# LED_Indicator.net
KiCad netlist of a schematic drawn in Altium Designer
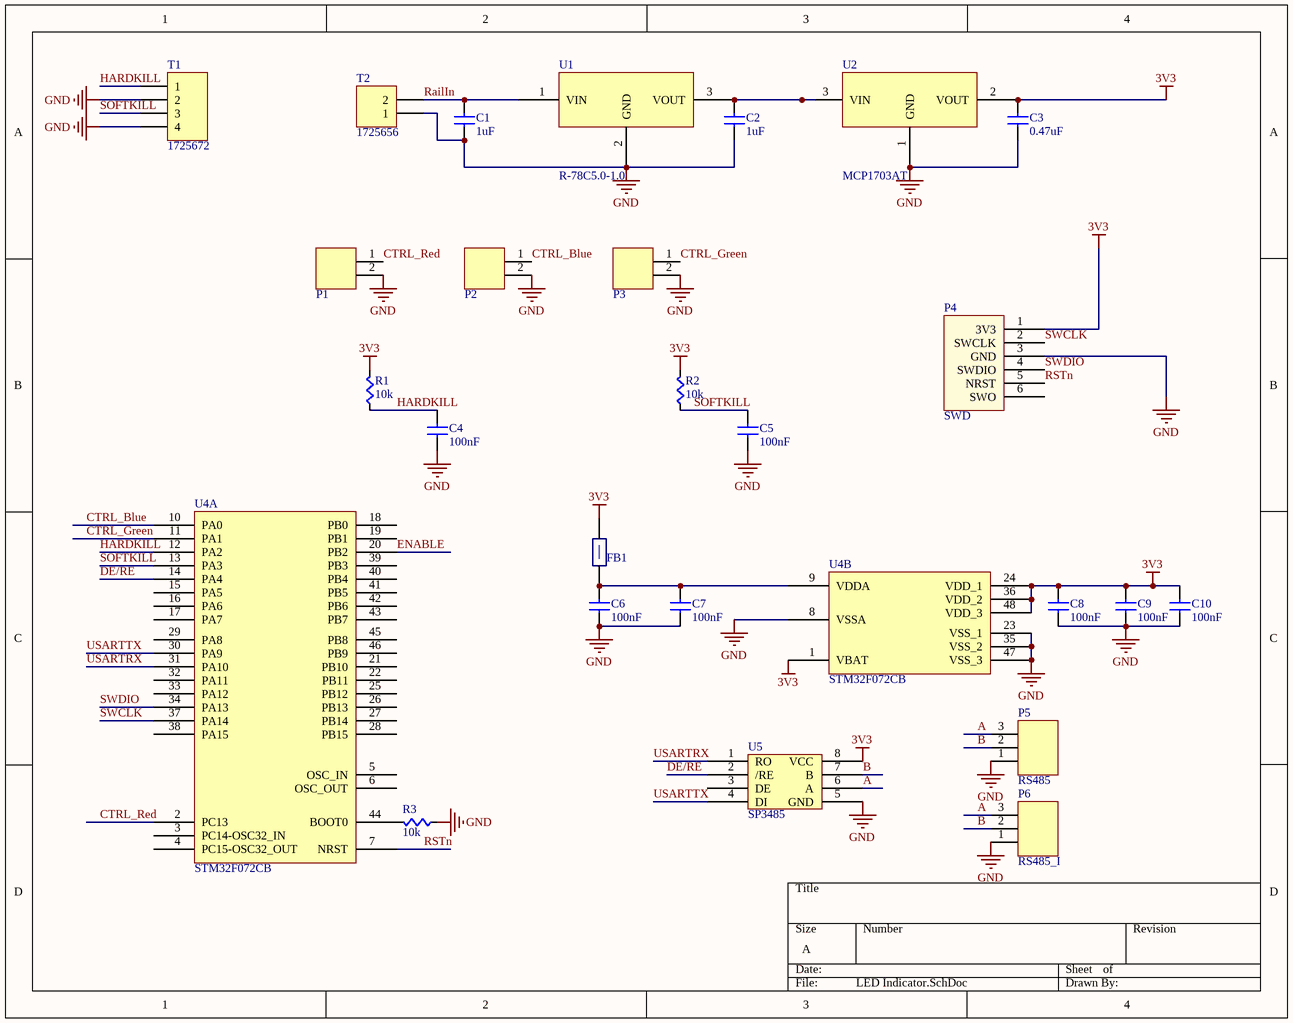
[diagram p0: LED Indicator.SchDoc]

(export (version "E")
  (design (tool "Eeschema 10.0.6"))
  (components
    (comp (ref "C1")
      (value "1uF")
      (footprint "CAPC0603")
      (fields (field (name "Comment") "Cap"))
      (libsource (lib "SubjuGator8") (part "Cap"))
    )
    (comp (ref "C2")
      (value "1uF")
      (footprint "CAPC0603")
      (fields (field (name "Comment") "Cap"))
      (libsource (lib "SubjuGator8") (part "Cap"))
    )
    (comp (ref "C3")
      (value "0.47uF")
      (footprint "CAPC0603")
      (fields (field (name "Comment") "Cap"))
      (libsource (lib "SubjuGator8") (part "Cap"))
    )
    (comp (ref "C4")
      (value "100nF")
      (footprint "CAPC0603")
      (fields (field (name "Comment") "Cap"))
      (libsource (lib "SubjuGator8") (part "Cap"))
    )
    (comp (ref "C5")
      (value "100nF")
      (footprint "CAPC0603")
      (fields (field (name "Comment") "Cap"))
      (libsource (lib "SubjuGator8") (part "Cap"))
    )
    (comp (ref "C6")
      (value "100nF")
      (footprint "CAPC0603")
      (fields (field (name "Comment") "Cap"))
      (libsource (lib "SubjuGator8") (part "Cap"))
    )
    (comp (ref "C7")
      (value "100nF")
      (footprint "CAPC0603")
      (fields (field (name "Comment") "Cap"))
      (libsource (lib "SubjuGator8") (part "Cap"))
    )
    (comp (ref "C8")
      (value "100nF")
      (footprint "CAPC0603")
      (fields (field (name "Comment") "Cap"))
      (libsource (lib "SubjuGator8") (part "Cap"))
    )
    (comp (ref "C9")
      (value "100nF")
      (footprint "CAPC0603")
      (fields (field (name "Comment") "Cap"))
      (libsource (lib "SubjuGator8") (part "Cap"))
    )
    (comp (ref "C10")
      (value "100nF")
      (footprint "CAPC0603")
      (fields (field (name "Comment") "Cap"))
      (libsource (lib "SubjuGator8") (part "Cap"))
    )
    (comp (ref "FB1")
      (value "FBead")
      (footprint "RES0603")
      (description "Ferrite Bead")
      (libsource (lib "SubjuGator8") (part "FBead"))
    )
    (comp (ref "P1")
      (value "2-pin Horz Sherlock")
      (footprint "MOLEX-HDR-1X2-SHERLOCK-HORZ")
      (fields
        (field (name "MANUFACTURER PART NUMBER") "0353630260")
        (field (name "MANUFACTURER") "Molex Inc")
      )
      (libsource (lib "SubjuGator8") (part "MOLEX-HDR-1x2-SHERLOCK_RA"))
    )
    (comp (ref "P2")
      (value "2-pin Horz Sherlock")
      (footprint "MOLEX-HDR-1X2-SHERLOCK-HORZ")
      (fields
        (field (name "MANUFACTURER PART NUMBER") "0353630260")
        (field (name "MANUFACTURER") "Molex Inc")
      )
      (libsource (lib "SubjuGator8") (part "MOLEX-HDR-1x2-SHERLOCK_RA"))
    )
    (comp (ref "P3")
      (value "2-pin Horz Sherlock")
      (footprint "MOLEX-HDR-1X2-SHERLOCK-HORZ")
      (fields
        (field (name "MANUFACTURER PART NUMBER") "0353630260")
        (field (name "MANUFACTURER") "Molex Inc")
      )
      (libsource (lib "SubjuGator8") (part "MOLEX-HDR-1x2-SHERLOCK_RA"))
    )
    (comp (ref "P4")
      (value "SWD")
      (footprint "SWD_STM32")
      (description "SWD connector matching the pinout on STM Discovery Boards")
      (libsource (lib "SubjuGator8") (part "SWD_STM32"))
    )
    (comp (ref "P5")
      (value "RS485")
      (footprint "MOLEX-HDR-1X3-SHERLOCK-RA")
      (description "Header, Molex, 2mm Pitch Sherlock Header, Single Row, Right Angle 3 Circuits, Length 3.3mm")
      (fields
        (field (name "MANUFACTURER PART NUMBER") "35363-0360")
        (field (name "MANUFACTURER") "Molex Connector Corporation")
      )
      (libsource (lib "SubjuGator8") (part "MOLEX-HDR-1x3-SHERLOCK_RA"))
    )
    (comp (ref "P6")
      (value "RS485_I")
      (footprint "MOLEX-HDR-1X3-SHERLOCK-RA")
      (description "Header, Molex, 2mm Pitch Sherlock Header, Single Row, Right Angle 3 Circuits, Length 3.3mm")
      (fields
        (field (name "MANUFACTURER PART NUMBER") "35363-0360")
        (field (name "MANUFACTURER") "Molex Connector Corporation")
      )
      (libsource (lib "SubjuGator8") (part "MOLEX-HDR-1x3-SHERLOCK_RA"))
    )
    (comp (ref "R1")
      (value "10k")
      (footprint "RES0603")
      (fields (field (name "Comment") "Res"))
      (libsource (lib "SubjuGator8") (part "Res"))
    )
    (comp (ref "R2")
      (value "10k")
      (footprint "RES0603")
      (fields (field (name "Comment") "Res"))
      (libsource (lib "SubjuGator8") (part "Res"))
    )
    (comp (ref "R3")
      (value "10k")
      (footprint "RES0603")
      (fields (field (name "Comment") "Res"))
      (libsource (lib "SubjuGator8") (part "Res"))
    )
    (comp (ref "T1")
      (value "1725672")
      (footprint "1725672")
      (description "CONN TERM BLOCK 2.54MM 4POS")
      (libsource (lib "SubjuGator8") (part "1725672"))
    )
    (comp (ref "T2")
      (value "1725656")
      (footprint "1725656")
      (description "CONN TERM BLOCK 2.54MM 2POS")
      (libsource (lib "SubjuGator8") (part "1725656"))
    )
    (comp (ref "U1")
      (value "R-78C5.0-1.0")
      (footprint "R-78C5.0-1.0")
      (description "CONV DC/DC 1A 5V OUT SIP VERT")
      (libsource (lib "SubjuGator8") (part "R-78C5.0-1.0"))
    )
    (comp (ref "U2")
      (value "MCP1703AT")
      (footprint "MCP1703AT-xx02EDB")
      (description "250 mA, 16V, Low Quiescent Current LDO Regulator")
      (libsource (lib "SubjuGator8") (part "MCP1703AT"))
    )
    (comp (ref "U4")
      (value "STM32F072CB")
      (footprint "STM32F072CB")
      (description "MCU 32BIT 128KB FLASH 48LQFP")
      (libsource (lib "SubjuGator8") (part "STM32F072CB"))
    )
    (comp (ref "U5")
      (value "SP3485")
      (footprint "SP3485")
      (description "IC TXRX RS485 HALF DUPLEX 8NSOIC")
      (libsource (lib "SubjuGator8") (part "SP3485"))
    )
  )
  (nets
    (net (code "1") (name "/A") (class "Default")
      (node (ref "P5") (pin "3") (pinfunction "3_3") (pintype "passive"))
      (node (ref "P6") (pin "3") (pinfunction "3_3") (pintype "passive"))
      (node (ref "U5") (pin "6") (pinfunction "A_6") (pintype "passive"))
    )
    (net (code "2") (name "/B") (class "Default")
      (node (ref "P5") (pin "2") (pinfunction "2_2") (pintype "passive"))
      (node (ref "P6") (pin "2") (pinfunction "2_2") (pintype "passive"))
      (node (ref "U5") (pin "7") (pinfunction "B_7") (pintype "passive"))
    )
    (net (code "3") (name "/CTRL_Blue") (class "Default")
      (node (ref "P2") (pin "1") (pinfunction "1_1") (pintype "passive"))
      (node (ref "U4") (pin "10") (pinfunction "PA0_10") (pintype "passive"))
    )
    (net (code "4") (name "/CTRL_Green") (class "Default")
      (node (ref "P3") (pin "1") (pinfunction "1_1") (pintype "passive"))
      (node (ref "U4") (pin "11") (pinfunction "PA1_11") (pintype "passive"))
    )
    (net (code "5") (name "/CTRL_Red") (class "Default")
      (node (ref "P1") (pin "1") (pinfunction "1_1") (pintype "passive"))
      (node (ref "U4") (pin "2") (pinfunction "PC13_2") (pintype "passive"))
    )
    (net (code "6") (name "/DE{slash}RE") (class "Default")
      (node (ref "U4") (pin "14") (pinfunction "PA4_14") (pintype "passive"))
      (node (ref "U5") (pin "2") (pinfunction "/RE_2") (pintype "passive"))
    )
    (net (code "7") (name "/ENABLE") (class "Default")
      (node (ref "U4") (pin "20") (pinfunction "PB2_20") (pintype "passive"))
    )
    (net (code "8") (name "/HARDKILL") (class "Default")
      (node (ref "C4") (pin "1") (pinfunction "A_1") (pintype "passive"))
      (node (ref "R1") (pin "2") (pinfunction "B_2") (pintype "passive"))
      (node (ref "T1") (pin "1") (pinfunction "1_1") (pintype "passive"))
      (node (ref "U4") (pin "12") (pinfunction "PA2_12") (pintype "passive"))
    )
    (net (code "9") (name "/RSTn") (class "Default")
      (node (ref "P4") (pin "5") (pinfunction "NRST_5") (pintype "passive"))
      (node (ref "U4") (pin "7") (pinfunction "NRST_7") (pintype "passive"))
    )
    (net (code "10") (name "/RailIn") (class "Default")
      (node (ref "C1") (pin "1") (pinfunction "A_1") (pintype "passive"))
      (node (ref "T2") (pin "2") (pinfunction "2_2") (pintype "passive"))
      (node (ref "U1") (pin "1") (pinfunction "VIN_1") (pintype "passive"))
    )
    (net (code "11") (name "/SOFTKILL") (class "Default")
      (node (ref "C5") (pin "1") (pinfunction "A_1") (pintype "passive"))
      (node (ref "R2") (pin "2") (pinfunction "B_2") (pintype "passive"))
      (node (ref "T1") (pin "3") (pinfunction "3_3") (pintype "passive"))
      (node (ref "U4") (pin "13") (pinfunction "PA3_13") (pintype "passive"))
    )
    (net (code "12") (name "/SWCLK") (class "Default")
      (node (ref "P4") (pin "2") (pinfunction "SWCLK_2") (pintype "passive"))
      (node (ref "U4") (pin "37") (pinfunction "PA14_37") (pintype "passive"))
    )
    (net (code "13") (name "/SWDIO") (class "Default")
      (node (ref "P4") (pin "4") (pinfunction "SWDIO_4") (pintype "passive"))
      (node (ref "U4") (pin "34") (pinfunction "PA13_34") (pintype "passive"))
    )
    (net (code "14") (name "/USARTRX") (class "Default")
      (node (ref "U4") (pin "31") (pinfunction "PA10_31") (pintype "passive"))
      (node (ref "U5") (pin "1") (pinfunction "RO_1") (pintype "passive"))
    )
    (net (code "15") (name "/USARTTX") (class "Default")
      (node (ref "U4") (pin "30") (pinfunction "PA9_30") (pintype "passive"))
      (node (ref "U5") (pin "4") (pinfunction "DI_4") (pintype "passive"))
    )
    (net (code "16") (name "3V3") (class "Default")
      (node (ref "C10") (pin "1") (pinfunction "A_1") (pintype "passive"))
      (node (ref "C3") (pin "1") (pinfunction "A_1") (pintype "passive"))
      (node (ref "C8") (pin "1") (pinfunction "A_1") (pintype "passive"))
      (node (ref "C9") (pin "1") (pinfunction "A_1") (pintype "passive"))
      (node (ref "FB1") (pin "2") (pinfunction "B_2") (pintype "passive"))
      (node (ref "P4") (pin "1") (pinfunction "3V3_1") (pintype "passive"))
      (node (ref "R1") (pin "1") (pinfunction "A_1") (pintype "passive"))
      (node (ref "R2") (pin "1") (pinfunction "A_1") (pintype "passive"))
      (node (ref "U2") (pin "2") (pinfunction "VOUT_2") (pintype "passive"))
      (node (ref "U4") (pin "1") (pinfunction "VBAT_1") (pintype "passive"))
      (node (ref "U4") (pin "24") (pinfunction "VDD_1_24") (pintype "passive"))
      (node (ref "U4") (pin "36") (pinfunction "VDD_2_36") (pintype "passive"))
      (node (ref "U4") (pin "48") (pinfunction "VDD_3_48") (pintype "passive"))
      (node (ref "U5") (pin "8") (pinfunction "VCC_8") (pintype "passive"))
    )
    (net (code "17") (name "GND") (class "Default")
      (node (ref "C1") (pin "2") (pinfunction "B_2") (pintype "passive"))
      (node (ref "C10") (pin "2") (pinfunction "B_2") (pintype "passive"))
      (node (ref "C2") (pin "2") (pinfunction "B_2") (pintype "passive"))
      (node (ref "C3") (pin "2") (pinfunction "B_2") (pintype "passive"))
      (node (ref "C4") (pin "2") (pinfunction "B_2") (pintype "passive"))
      (node (ref "C5") (pin "2") (pinfunction "B_2") (pintype "passive"))
      (node (ref "C6") (pin "2") (pinfunction "B_2") (pintype "passive"))
      (node (ref "C7") (pin "2") (pinfunction "B_2") (pintype "passive"))
      (node (ref "C8") (pin "2") (pinfunction "B_2") (pintype "passive"))
      (node (ref "C9") (pin "2") (pinfunction "B_2") (pintype "passive"))
      (node (ref "P1") (pin "2") (pinfunction "2_2") (pintype "passive"))
      (node (ref "P2") (pin "2") (pinfunction "2_2") (pintype "passive"))
      (node (ref "P3") (pin "2") (pinfunction "2_2") (pintype "passive"))
      (node (ref "P4") (pin "3") (pinfunction "GND_3") (pintype "passive"))
      (node (ref "P5") (pin "1") (pinfunction "1_1") (pintype "passive"))
      (node (ref "P6") (pin "1") (pinfunction "1_1") (pintype "passive"))
      (node (ref "R3") (pin "2") (pinfunction "B_2") (pintype "passive"))
      (node (ref "T1") (pin "2") (pinfunction "2_2") (pintype "passive"))
      (node (ref "T1") (pin "4") (pinfunction "4_4") (pintype "passive"))
      (node (ref "T2") (pin "1") (pinfunction "1_1") (pintype "passive"))
      (node (ref "U1") (pin "2") (pinfunction "GND_2") (pintype "power_in"))
      (node (ref "U2") (pin "1") (pinfunction "GND_1") (pintype "power_in"))
      (node (ref "U4") (pin "23") (pinfunction "VSS_1_23") (pintype "passive"))
      (node (ref "U4") (pin "35") (pinfunction "VSS_2_35") (pintype "passive"))
      (node (ref "U4") (pin "47") (pinfunction "VSS_3_47") (pintype "passive"))
      (node (ref "U4") (pin "8") (pinfunction "VSSA_8") (pintype "passive"))
      (node (ref "U5") (pin "5") (pinfunction "GND_5") (pintype "passive"))
    )
    (net (code "18") (name "Net-(C2-A)") (class "Default")
      (node (ref "C2") (pin "1") (pinfunction "A_1") (pintype "passive"))
      (node (ref "U1") (pin "3") (pinfunction "VOUT_3") (pintype "passive"))
      (node (ref "U2") (pin "3") (pinfunction "VIN_3") (pintype "passive"))
    )
    (net (code "19") (name "Net-(C6-A)") (class "Default")
      (node (ref "C6") (pin "1") (pinfunction "A_1") (pintype "passive"))
      (node (ref "C7") (pin "1") (pinfunction "A_1") (pintype "passive"))
      (node (ref "FB1") (pin "1") (pinfunction "A_1") (pintype "passive"))
      (node (ref "U4") (pin "9") (pinfunction "VDDA_9") (pintype "passive"))
    )
    (net (code "20") (name "Net-(R3-A)") (class "Default")
      (node (ref "R3") (pin "1") (pinfunction "A_1") (pintype "passive"))
      (node (ref "U4") (pin "44") (pinfunction "BOOT0_44") (pintype "passive"))
    )
    (net (code "21") (name "unconnected-(P4-SWO-Pad6)") (class "Default")
      (node (ref "P4") (pin "6") (pinfunction "SWO_6") (pintype "passive"))
    )
    (net (code "22") (name "unconnected-(U4A-OSC_IN-Pad5)") (class "Default")
      (node (ref "U4") (pin "5") (pinfunction "OSC_IN_5") (pintype "passive"))
    )
    (net (code "23") (name "unconnected-(U4A-OSC_OUT-Pad6)") (class "Default")
      (node (ref "U4") (pin "6") (pinfunction "OSC_OUT_6") (pintype "passive"))
    )
    (net (code "24") (name "unconnected-(U4A-PA5-Pad15)") (class "Default")
      (node (ref "U4") (pin "15") (pinfunction "PA5_15") (pintype "passive"))
    )
    (net (code "25") (name "unconnected-(U4A-PA6-Pad16)") (class "Default")
      (node (ref "U4") (pin "16") (pinfunction "PA6_16") (pintype "passive"))
    )
    (net (code "26") (name "unconnected-(U4A-PA7-Pad17)") (class "Default")
      (node (ref "U4") (pin "17") (pinfunction "PA7_17") (pintype "passive"))
    )
    (net (code "27") (name "unconnected-(U4A-PA8-Pad29)") (class "Default")
      (node (ref "U4") (pin "29") (pinfunction "PA8_29") (pintype "passive"))
    )
    (net (code "28") (name "unconnected-(U4A-PA11-Pad32)") (class "Default")
      (node (ref "U4") (pin "32") (pinfunction "PA11_32") (pintype "passive"))
    )
    (net (code "29") (name "unconnected-(U4A-PA12-Pad33)") (class "Default")
      (node (ref "U4") (pin "33") (pinfunction "PA12_33") (pintype "passive"))
    )
    (net (code "30") (name "unconnected-(U4A-PA15-Pad38)") (class "Default")
      (node (ref "U4") (pin "38") (pinfunction "PA15_38") (pintype "passive"))
    )
    (net (code "31") (name "unconnected-(U4A-PB0-Pad18)") (class "Default")
      (node (ref "U4") (pin "18") (pinfunction "PB0_18") (pintype "passive"))
    )
    (net (code "32") (name "unconnected-(U4A-PB1-Pad19)") (class "Default")
      (node (ref "U4") (pin "19") (pinfunction "PB1_19") (pintype "passive"))
    )
    (net (code "33") (name "unconnected-(U4A-PB3-Pad39)") (class "Default")
      (node (ref "U4") (pin "39") (pinfunction "PB3_39") (pintype "passive"))
    )
    (net (code "34") (name "unconnected-(U4A-PB4-Pad40)") (class "Default")
      (node (ref "U4") (pin "40") (pinfunction "PB4_40") (pintype "passive"))
    )
    (net (code "35") (name "unconnected-(U4A-PB5-Pad41)") (class "Default")
      (node (ref "U4") (pin "41") (pinfunction "PB5_41") (pintype "passive"))
    )
    (net (code "36") (name "unconnected-(U4A-PB6-Pad42)") (class "Default")
      (node (ref "U4") (pin "42") (pinfunction "PB6_42") (pintype "passive"))
    )
    (net (code "37") (name "unconnected-(U4A-PB7-Pad43)") (class "Default")
      (node (ref "U4") (pin "43") (pinfunction "PB7_43") (pintype "passive"))
    )
    (net (code "38") (name "unconnected-(U4A-PB8-Pad45)") (class "Default")
      (node (ref "U4") (pin "45") (pinfunction "PB8_45") (pintype "passive"))
    )
    (net (code "39") (name "unconnected-(U4A-PB9-Pad46)") (class "Default")
      (node (ref "U4") (pin "46") (pinfunction "PB9_46") (pintype "passive"))
    )
    (net (code "40") (name "unconnected-(U4A-PB10-Pad21)") (class "Default")
      (node (ref "U4") (pin "21") (pinfunction "PB10_21") (pintype "passive"))
    )
    (net (code "41") (name "unconnected-(U4A-PB11-Pad22)") (class "Default")
      (node (ref "U4") (pin "22") (pinfunction "PB11_22") (pintype "passive"))
    )
    (net (code "42") (name "unconnected-(U4A-PB12-Pad25)") (class "Default")
      (node (ref "U4") (pin "25") (pinfunction "PB12_25") (pintype "passive"))
    )
    (net (code "43") (name "unconnected-(U4A-PB13-Pad26)") (class "Default")
      (node (ref "U4") (pin "26") (pinfunction "PB13_26") (pintype "passive"))
    )
    (net (code "44") (name "unconnected-(U4A-PB14-Pad27)") (class "Default")
      (node (ref "U4") (pin "27") (pinfunction "PB14_27") (pintype "passive"))
    )
    (net (code "45") (name "unconnected-(U4A-PB15-Pad28)") (class "Default")
      (node (ref "U4") (pin "28") (pinfunction "PB15_28") (pintype "passive"))
    )
    (net (code "46") (name "unconnected-(U4A-PC14-OSC32_IN-Pad3)") (class "Default")
      (node (ref "U4") (pin "3") (pinfunction "PC14-OSC32_IN_3") (pintype "passive"))
    )
    (net (code "47") (name "unconnected-(U4A-PC15-OSC32_OUT-Pad4)") (class "Default")
      (node (ref "U4") (pin "4") (pinfunction "PC15-OSC32_OUT_4") (pintype "passive"))
    )
    (net (code "48") (name "unconnected-(U5-DE-Pad3)") (class "Default")
      (node (ref "U5") (pin "3") (pinfunction "DE_3") (pintype "passive"))
    )
  )
)
